# Pi2Display.net
KiCad netlist of a schematic drawn in EAGLE
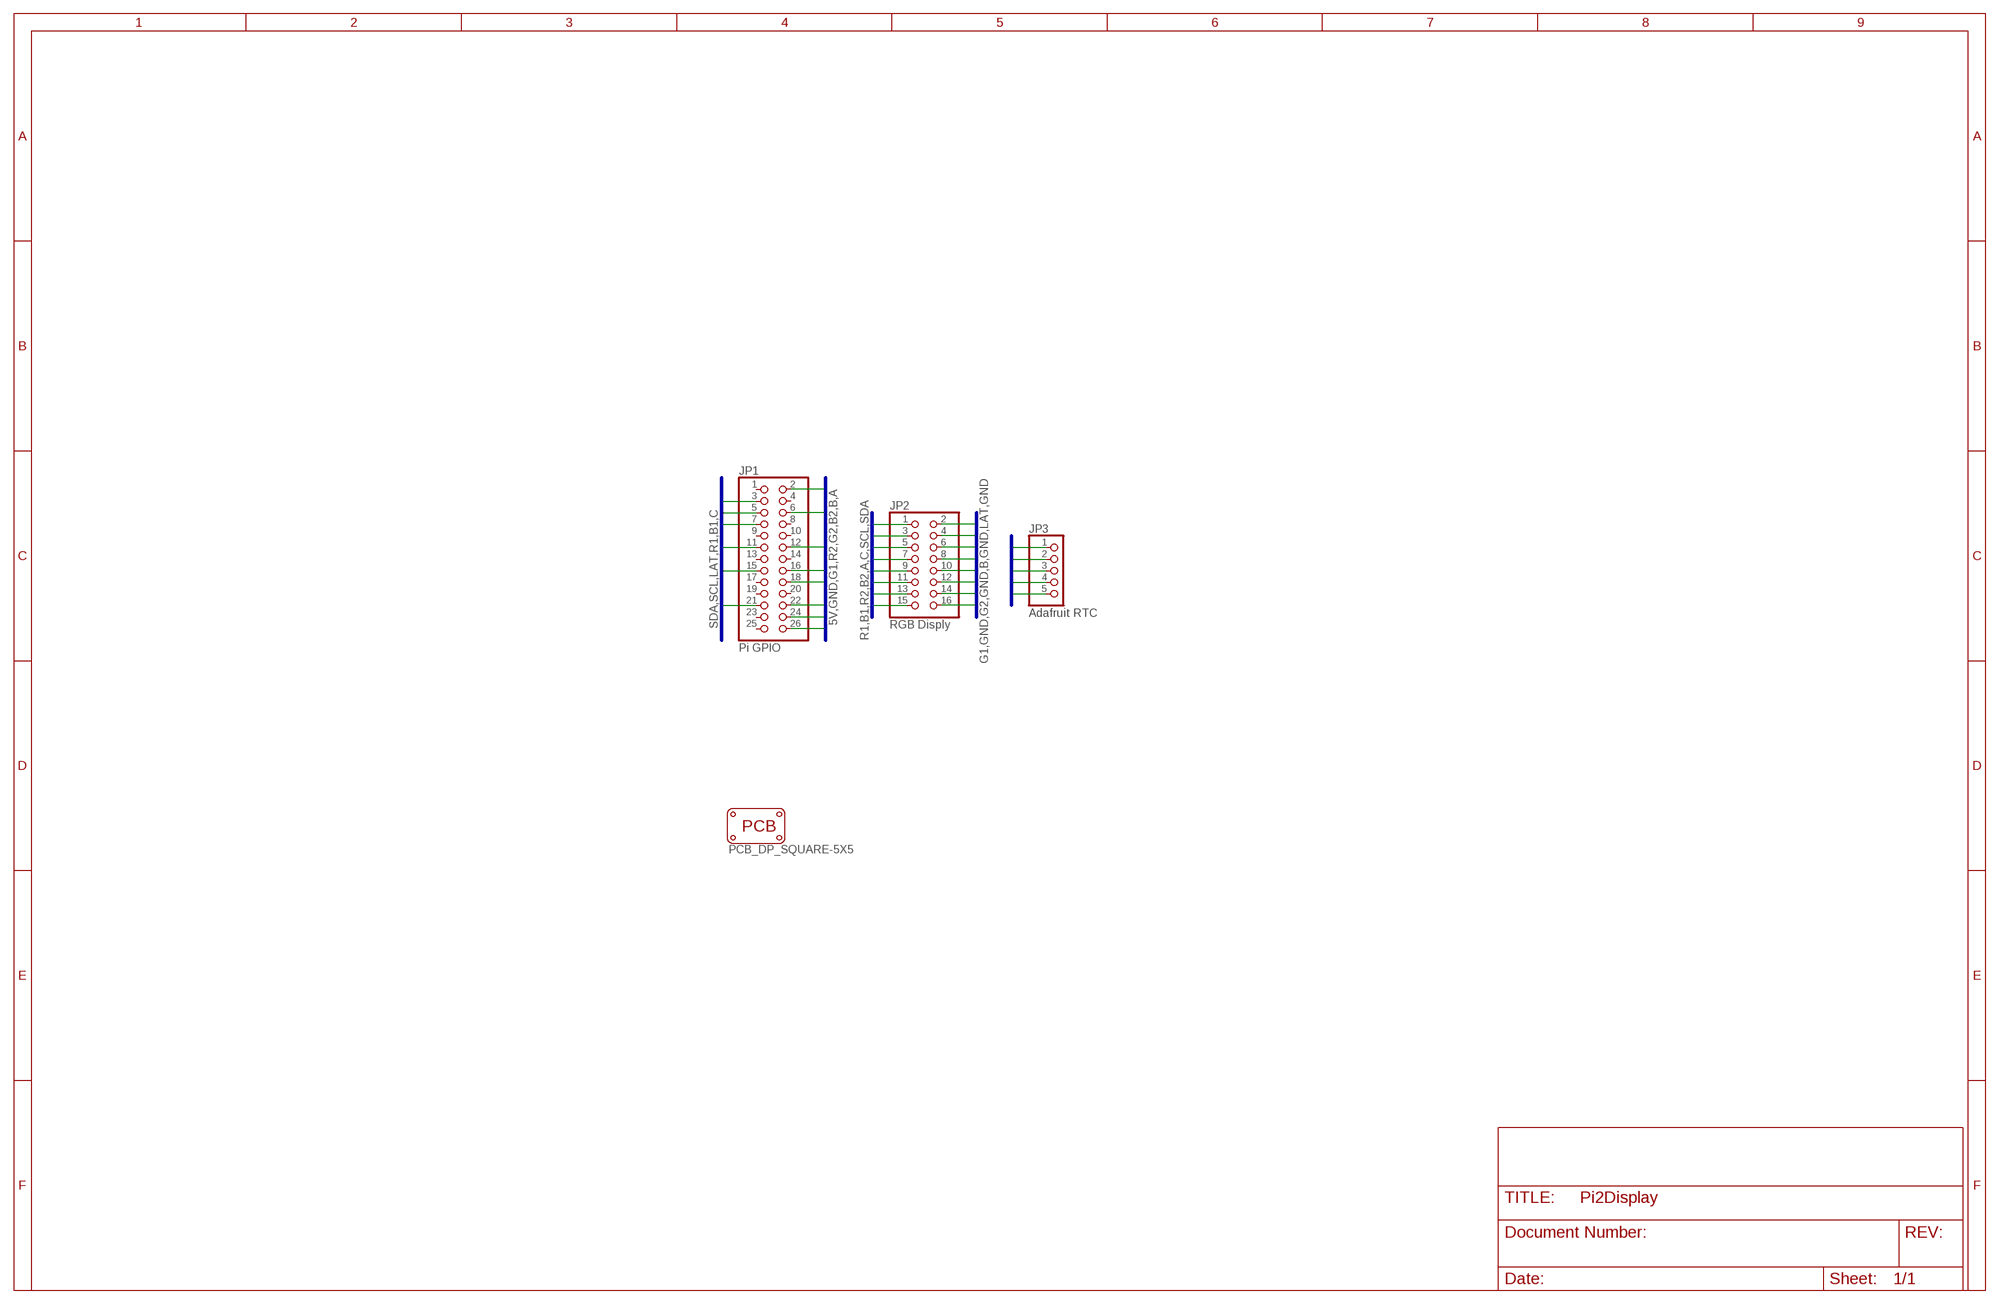
[diagram p0: schematic, sheet 1]

(export (version "E")
  (design (tool "Eeschema 10.0.6"))
  (components
    (comp (ref "JP1")
      (value "Pi GPIO")
      (footprint "eagle-import:2X13")
      (libsource (lib "eagle-import") (part "PINHD-2X13"))
    )
    (comp (ref "JP2")
      (value "RGB Disply")
      (footprint "eagle-import:2X08")
      (libsource (lib "eagle-import") (part "PINHD-2X8"))
    )
    (comp (ref "JP3")
      (value "Adafruit RTC")
      (footprint "eagle-import:1X05")
      (libsource (lib "eagle-import") (part "PINHD-1X5"))
    )
    (comp (ref "PCB1")
      (value "PCB_DP_SQUARE-5X5")
      (footprint "eagle-import:DP5050_V1")
      (libsource (lib "eagle-import") (part "PCB_DP_SQUARE-5X5"))
    )
  )
  (nets
    (net (code "1") (name "/5V") (class "Default")
      (node (ref "JP1") (pin "2") (pinfunction "2_2") (pintype "passive"))
      (node (ref "JP3") (pin "2") (pinfunction "2_2") (pintype "passive"))
    )
    (net (code "2") (name "/A") (class "Default")
      (node (ref "JP1") (pin "26") (pinfunction "26_26") (pintype "passive"))
      (node (ref "JP2") (pin "9") (pinfunction "9_9") (pintype "passive"))
    )
    (net (code "3") (name "/B") (class "Default")
      (node (ref "JP1") (pin "24") (pinfunction "24_24") (pintype "passive"))
      (node (ref "JP2") (pin "10") (pinfunction "10_10") (pintype "passive"))
    )
    (net (code "4") (name "/B1") (class "Default")
      (node (ref "JP1") (pin "15") (pinfunction "15_15") (pintype "passive"))
      (node (ref "JP2") (pin "3") (pinfunction "3_3") (pintype "passive"))
    )
    (net (code "5") (name "/B2") (class "Default")
      (node (ref "JP1") (pin "22") (pinfunction "22_22") (pintype "passive"))
      (node (ref "JP2") (pin "7") (pinfunction "7_7") (pintype "passive"))
    )
    (net (code "6") (name "/C") (class "Default")
      (node (ref "JP1") (pin "21") (pinfunction "21_21") (pintype "passive"))
      (node (ref "JP2") (pin "11") (pinfunction "11_11") (pintype "passive"))
    )
    (net (code "7") (name "/G1") (class "Default")
      (node (ref "JP1") (pin "12") (pinfunction "12_12") (pintype "passive"))
      (node (ref "JP2") (pin "2") (pinfunction "2_2") (pintype "passive"))
    )
    (net (code "8") (name "/G2") (class "Default")
      (node (ref "JP1") (pin "18") (pinfunction "18_18") (pintype "passive"))
      (node (ref "JP2") (pin "6") (pinfunction "6_6") (pintype "passive"))
    )
    (net (code "9") (name "/GND") (class "Default")
      (node (ref "JP1") (pin "6") (pinfunction "6_6") (pintype "passive"))
      (node (ref "JP2") (pin "12") (pinfunction "12_12") (pintype "passive"))
      (node (ref "JP2") (pin "16") (pinfunction "16_16") (pintype "passive"))
      (node (ref "JP2") (pin "4") (pinfunction "4_4") (pintype "passive"))
      (node (ref "JP2") (pin "8") (pinfunction "8_8") (pintype "passive"))
      (node (ref "JP3") (pin "1") (pinfunction "1_1") (pintype "passive"))
    )
    (net (code "10") (name "/LAT") (class "Default")
      (node (ref "JP1") (pin "7") (pinfunction "7_7") (pintype "passive"))
      (node (ref "JP2") (pin "14") (pinfunction "14_14") (pintype "passive"))
    )
    (net (code "11") (name "/R1") (class "Default")
      (node (ref "JP1") (pin "11") (pinfunction "11_11") (pintype "passive"))
      (node (ref "JP2") (pin "1") (pinfunction "1_1") (pintype "passive"))
    )
    (net (code "12") (name "/R2") (class "Default")
      (node (ref "JP1") (pin "16") (pinfunction "16_16") (pintype "passive"))
      (node (ref "JP2") (pin "5") (pinfunction "5_5") (pintype "passive"))
    )
    (net (code "13") (name "/SCL") (class "Default")
      (node (ref "JP1") (pin "5") (pinfunction "5_5") (pintype "passive"))
      (node (ref "JP2") (pin "13") (pinfunction "13_13") (pintype "passive"))
      (node (ref "JP3") (pin "4") (pinfunction "4_4") (pintype "passive"))
    )
    (net (code "14") (name "/SDA") (class "Default")
      (node (ref "JP1") (pin "3") (pinfunction "3_3") (pintype "passive"))
      (node (ref "JP2") (pin "15") (pinfunction "15_15") (pintype "passive"))
      (node (ref "JP3") (pin "3") (pinfunction "3_3") (pintype "passive"))
    )
    (net (code "19") (name "unconnected-(JP1-Pad1)") (class "Default")
      (node (ref "JP1") (pin "1") (pinfunction "1_1") (pintype "passive"))
    )
    (net (code "20") (name "unconnected-(JP1-Pad4)") (class "Default")
      (node (ref "JP1") (pin "4") (pinfunction "4_4") (pintype "passive"))
    )
    (net (code "21") (name "unconnected-(JP1-Pad8)") (class "Default")
      (node (ref "JP1") (pin "8") (pinfunction "8_8") (pintype "passive"))
    )
    (net (code "22") (name "unconnected-(JP1-Pad9)") (class "Default")
      (node (ref "JP1") (pin "9") (pinfunction "9_9") (pintype "passive"))
    )
    (net (code "23") (name "unconnected-(JP1-Pad10)") (class "Default")
      (node (ref "JP1") (pin "10") (pinfunction "10_10") (pintype "passive"))
    )
    (net (code "24") (name "unconnected-(JP1-Pad13)") (class "Default")
      (node (ref "JP1") (pin "13") (pinfunction "13_13") (pintype "passive"))
    )
    (net (code "25") (name "unconnected-(JP1-Pad14)") (class "Default")
      (node (ref "JP1") (pin "14") (pinfunction "14_14") (pintype "passive"))
    )
    (net (code "26") (name "unconnected-(JP1-Pad17)") (class "Default")
      (node (ref "JP1") (pin "17") (pinfunction "17_17") (pintype "passive"))
    )
    (net (code "27") (name "unconnected-(JP1-Pad19)") (class "Default")
      (node (ref "JP1") (pin "19") (pinfunction "19_19") (pintype "passive"))
    )
    (net (code "28") (name "unconnected-(JP1-Pad20)") (class "Default")
      (node (ref "JP1") (pin "20") (pinfunction "20_20") (pintype "passive"))
    )
    (net (code "29") (name "unconnected-(JP1-Pad23)") (class "Default")
      (node (ref "JP1") (pin "23") (pinfunction "23_23") (pintype "passive"))
    )
    (net (code "30") (name "unconnected-(JP1-Pad25)") (class "Default")
      (node (ref "JP1") (pin "25") (pinfunction "25_25") (pintype "passive"))
    )
    (net (code "31") (name "unconnected-(JP3-Pad5)") (class "Default")
      (node (ref "JP3") (pin "5") (pinfunction "5_5") (pintype "passive"))
    )
  )
)
